# InputMicroproduct.net
KiCad netlist of a schematic drawn in Altium Designer
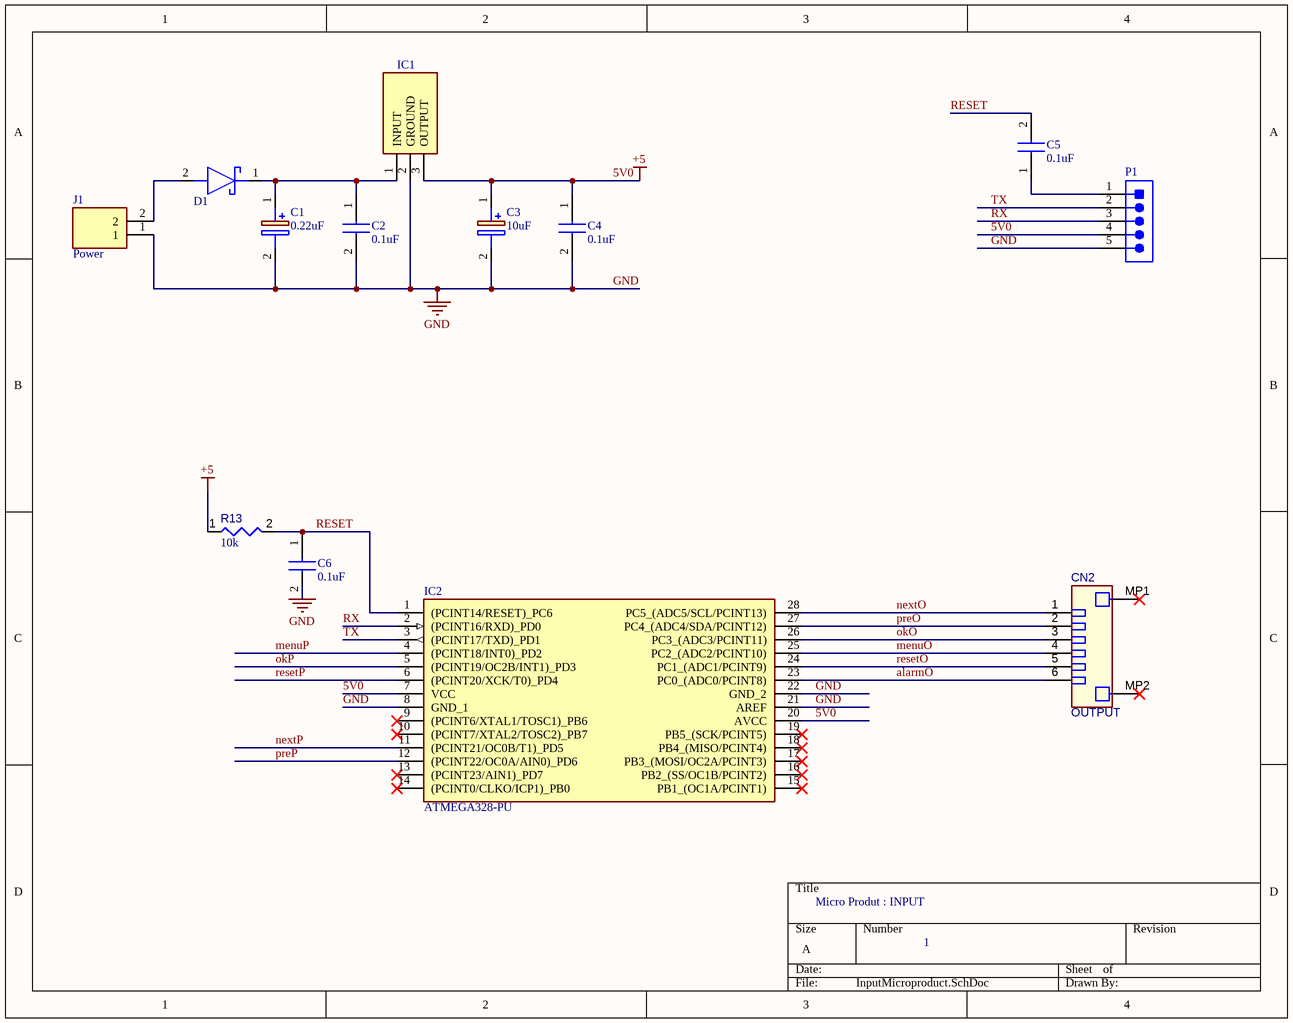
[diagram p0: InputMicroproduct.SchDoc]

(export (version "E")
  (design (tool "Eeschema 10.0.6"))
  (components
    (comp (ref "C1")
      (value "0.22uF")
      (footprint "SamacSys:CAPPRD200W52D500H1250")
      (description "Capacitor Polarised")
      (fields
        (field (name "MANUFACTURER_PART_NUMBER") "860010772002")
        (field (name "MOUSER PART NUMBER") "710-860010772002")
      )
      (libsource (lib "*") (part "860010772002"))
    )
    (comp (ref "C2")
      (value "0.1uF")
      (footprint "SamacSys:S104Z93Z5VL83L0R")
      (description "Capacitor")
      (fields
        (field (name "MANUFACTURER_PART_NUMBER") "S104Z93Z5VL83L0R")
        (field (name "MOUSER PART NUMBER") "594-S104Z93Z5VL83L0R")
      )
      (libsource (lib "*") (part "S104Z93Z5VL83L0R"))
    )
    (comp (ref "C3")
      (value "10uF")
      (footprint "SamacSys:CAPPRD200W55D500H1250")
      (description "Capacitor Polarised")
      (fields (field (name "MANUFACTURER_PART_NUMBER") "EEUFR1H100"))
      (libsource (lib "*") (part "EEUFR1H100"))
    )
    (comp (ref "C4")
      (value "0.1uF")
      (footprint "SamacSys:S104Z93Z5VL83L0R")
      (description "Capacitor")
      (fields
        (field (name "MANUFACTURER_PART_NUMBER") "S104Z93Z5VL83L0R")
        (field (name "MOUSER PART NUMBER") "594-S104Z93Z5VL83L0R")
      )
      (libsource (lib "*") (part "S104Z93Z5VL83L0R"))
    )
    (comp (ref "C5")
      (value "0.1uF")
      (footprint "SamacSys:S104Z93Z5VL83L0R")
      (description "Capacitor")
      (fields
        (field (name "MANUFACTURER_PART_NUMBER") "S104Z93Z5VL83L0R")
        (field (name "MOUSER PART NUMBER") "594-S104Z93Z5VL83L0R")
      )
      (libsource (lib "*") (part "S104Z93Z5VL83L0R"))
    )
    (comp (ref "C6")
      (value "0.1uF")
      (footprint "SamacSys:S104Z93Z5VL83L0R")
      (description "Capacitor")
      (fields
        (field (name "MANUFACTURER_PART_NUMBER") "S104Z93Z5VL83L0R")
        (field (name "MOUSER PART NUMBER") "594-S104Z93Z5VL83L0R")
      )
      (libsource (lib "*") (part "S104Z93Z5VL83L0R"))
    )
    (comp (ref "CN2")
      (value "OUTPUT")
      (footprint "JST-BM06B-SRSS-TB_V")
      (description "Header, Pitch 1 mm, 1 x 6 Position, Height 4.25 mm, -25 to 85 degC")
      (libsource (lib "University of Moratuwa") (part "CMP-00143-5"))
    )
    (comp (ref "D1")
      (value "Protection Diode")
      (footprint "SamacSys:DIOAD950W60L350D150")
      (description "Schottky Diode")
      (fields
        (field (name "MANUFACTURER_PART_NUMBER") "SD103A-TR")
        (field (name "MOUSER PART NUMBER") "625-SD103A")
      )
      (libsource (lib "*") (part "SD103A-TR"))
    )
    (comp (ref "IC1")
      (value "Power Regulator")
      (footprint "SamacSys:TO255P460X1020X2008-3P")
      (description "Integrated Circuit")
      (fields
        (field (name "MANUFACTURER_PART_NUMBER") "L7805CV")
        (field (name "MOUSER PART NUMBER") "511-L7805CV")
      )
      (libsource (lib "*") (part "L7805CV"))
    )
    (comp (ref "IC2")
      (value "ATMEGA328-PU")
      (footprint "SamacSys:DIP1016W53P254L3468H457Q28N")
      (description "Integrated Circuit")
      (fields (field (name "MOUSER PART NUMBER") "556-ATMEGA328-PU"))
      (libsource (lib "*") (part "ATMEGA328-PU"))
    )
    (comp (ref "J1")
      (value "1546215-2")
      (footprint "SamacSys:15462152")
      (description "Connector - Two pin (Power)")
      (fields (field (name "MOUSER PART NUMBER") "571-1546215-2") (field (name "TEXT") "Power"))
      (libsource (lib "*") (part "1546215-2"))
    )
    (comp (ref "P1")
      (value "77311-462K05LF")
      (footprint "FCI-77311-5_V")
      (fields (field (name "MANUFACTURER") "FCI Electronics"))
      (libsource (lib "University of Moratuwa") (part "CN-1P-M-R5"))
    )
    (comp (ref "R13")
      (value "10k")
      (footprint "RESA60-630X240")
      (description "Axial Resistor, 10 KOhm, +/- 1%, 0.25 W, -55 to 155 degC, 2-Pin THD, RoHS, Bulk")
      (fields (field (name "POWER") "250mW") (field (name "MANUFACTURER") "Yageo"))
      (libsource (lib "University of Moratuwa") (part "RES-2"))
    )
  )
  (nets
    (net (code "1") (name "+5") (class "Default")
      (node (ref "C3") (pin "1") (pinfunction "+_1") (pintype "passive"))
      (node (ref "C4") (pin "1") (pinfunction "1_1") (pintype "passive"))
      (node (ref "IC1") (pin "3") (pinfunction "OUTPUT_3") (pintype "passive"))
      (node (ref "IC2") (pin "20") (pinfunction "AVCC_20") (pintype "power_in"))
      (node (ref "IC2") (pin "7") (pinfunction "VCC_7") (pintype "power_in"))
      (node (ref "P1") (pin "4") (pinfunction "VCC_4") (pintype "passive"))
      (node (ref "R13") (pin "1") (pinfunction "1_1") (pintype "passive"))
    )
    (net (code "2") (name "/RESET") (class "Default")
      (node (ref "C5") (pin "2") (pinfunction "2_2") (pintype "passive"))
      (node (ref "C6") (pin "1") (pinfunction "1_1") (pintype "passive"))
      (node (ref "IC2") (pin "1") (pinfunction "(PCINT14/RESET)_PC6_1") (pintype "passive"))
      (node (ref "R13") (pin "2") (pinfunction "2_2") (pintype "passive"))
    )
    (net (code "3") (name "/RX") (class "Default")
      (node (ref "IC2") (pin "2") (pinfunction "(PCINT16/RXD)_PD0_2") (pintype "input"))
      (node (ref "P1") (pin "3") (pinfunction "TXO_3") (pintype "passive"))
    )
    (net (code "4") (name "/TX") (class "Default")
      (node (ref "IC2") (pin "3") (pinfunction "(PCINT17/TXD)_PD1_3") (pintype "output"))
      (node (ref "P1") (pin "2") (pinfunction "RXI_2") (pintype "passive"))
    )
    (net (code "5") (name "/alarmO") (class "Default")
      (node (ref "CN2") (pin "6") (pinfunction "6_6") (pintype "passive"))
      (node (ref "IC2") (pin "23") (pinfunction "PC0_(ADC0/PCINT8)_23") (pintype "passive"))
    )
    (net (code "6") (name "/menuO") (class "Default")
      (node (ref "CN2") (pin "4") (pinfunction "4_4") (pintype "passive"))
      (node (ref "IC2") (pin "25") (pinfunction "PC2_(ADC2/PCINT10)_25") (pintype "passive"))
    )
    (net (code "7") (name "/menuP") (class "Default")
      (node (ref "IC2") (pin "4") (pinfunction "(PCINT18/INT0)_PD2_4") (pintype "passive"))
    )
    (net (code "8") (name "/nextO") (class "Default")
      (node (ref "CN2") (pin "1") (pinfunction "1_1") (pintype "passive"))
      (node (ref "IC2") (pin "28") (pinfunction "PC5_(ADC5/SCL/PCINT13)_28") (pintype "passive"))
    )
    (net (code "9") (name "/nextP") (class "Default")
      (node (ref "IC2") (pin "11") (pinfunction "(PCINT21/OC0B/T1)_PD5_11") (pintype "passive"))
    )
    (net (code "10") (name "/okO") (class "Default")
      (node (ref "CN2") (pin "3") (pinfunction "3_3") (pintype "passive"))
      (node (ref "IC2") (pin "26") (pinfunction "PC3_(ADC3/PCINT11)_26") (pintype "passive"))
    )
    (net (code "11") (name "/okP") (class "Default")
      (node (ref "IC2") (pin "5") (pinfunction "(PCINT19/OC2B/INT1)_PD3_5") (pintype "passive"))
    )
    (net (code "12") (name "/preO") (class "Default")
      (node (ref "CN2") (pin "2") (pinfunction "2_2") (pintype "passive"))
      (node (ref "IC2") (pin "27") (pinfunction "PC4_(ADC4/SDA/PCINT12)_27") (pintype "passive"))
    )
    (net (code "13") (name "/preP") (class "Default")
      (node (ref "IC2") (pin "12") (pinfunction "(PCINT22/OC0A/AIN0)_PD6_12") (pintype "passive"))
    )
    (net (code "14") (name "/resetO") (class "Default")
      (node (ref "CN2") (pin "5") (pinfunction "5_5") (pintype "passive"))
      (node (ref "IC2") (pin "24") (pinfunction "PC1_(ADC1/PCINT9)_24") (pintype "passive"))
    )
    (net (code "15") (name "/resetP") (class "Default")
      (node (ref "IC2") (pin "6") (pinfunction "(PCINT20/XCK/T0)_PD4_6") (pintype "passive"))
    )
    (net (code "16") (name "GND") (class "Default")
      (node (ref "C1") (pin "2") (pinfunction "-_2") (pintype "passive"))
      (node (ref "C2") (pin "2") (pinfunction "2_2") (pintype "passive"))
      (node (ref "C3") (pin "2") (pinfunction "-_2") (pintype "passive"))
      (node (ref "C4") (pin "2") (pinfunction "2_2") (pintype "passive"))
      (node (ref "C6") (pin "2") (pinfunction "2_2") (pintype "passive"))
      (node (ref "IC1") (pin "2") (pinfunction "GROUND_2") (pintype "passive"))
      (node (ref "IC2") (pin "21") (pinfunction "AREF_21") (pintype "passive"))
      (node (ref "IC2") (pin "22") (pinfunction "GND_2_22") (pintype "power_in"))
      (node (ref "IC2") (pin "8") (pinfunction "GND_1_8") (pintype "power_in"))
      (node (ref "J1") (pin "1") (pinfunction "1_1") (pintype "passive"))
      (node (ref "P1") (pin "5") (pinfunction "CTS_5") (pintype "passive"))
    )
    (net (code "17") (name "Net-(C1-+)") (class "Default")
      (node (ref "C1") (pin "1") (pinfunction "+_1") (pintype "passive"))
      (node (ref "C2") (pin "1") (pinfunction "1_1") (pintype "passive"))
      (node (ref "D1") (pin "1") (pinfunction "K_1") (pintype "passive"))
      (node (ref "IC1") (pin "1") (pinfunction "INPUT_1") (pintype "passive"))
    )
    (net (code "18") (name "Net-(D1-A)") (class "Default")
      (node (ref "D1") (pin "2") (pinfunction "A_2") (pintype "passive"))
      (node (ref "J1") (pin "2") (pinfunction "2_2") (pintype "passive"))
    )
    (net (code "19") (name "Net-(P1-DTR)") (class "Default")
      (node (ref "C5") (pin "1") (pinfunction "1_1") (pintype "passive"))
      (node (ref "P1") (pin "1") (pinfunction "DTR_1") (pintype "passive"))
    )
    (net (code "20") (name "unconnected-(CN2-PadMP1)") (class "Default")
      (node (ref "CN2") (pin "MP1") (pinfunction "MP1_MP1") (pintype "passive+no_connect"))
    )
    (net (code "21") (name "unconnected-(CN2-PadMP2)") (class "Default")
      (node (ref "CN2") (pin "MP2") (pinfunction "MP2_MP2") (pintype "passive+no_connect"))
    )
    (net (code "22") (name "unconnected-(IC2-(PCINT0{slash}CLKO{slash}ICP1)_PB0-Pad14)") (class "Default")
      (node (ref "IC2") (pin "14") (pinfunction "(PCINT0/CLKO/ICP1)_PB0_14") (pintype "passive+no_connect"))
    )
    (net (code "23") (name "unconnected-(IC2-(PCINT6{slash}XTAL1{slash}TOSC1)_PB6-Pad9)") (class "Default")
      (node (ref "IC2") (pin "9") (pinfunction "(PCINT6/XTAL1/TOSC1)_PB6_9") (pintype "passive+no_connect"))
    )
    (net (code "24") (name "unconnected-(IC2-(PCINT7{slash}XTAL2{slash}TOSC2)_PB7-Pad10)") (class "Default")
      (node (ref "IC2") (pin "10") (pinfunction "(PCINT7/XTAL2/TOSC2)_PB7_10") (pintype "passive+no_connect"))
    )
    (net (code "25") (name "unconnected-(IC2-(PCINT23{slash}AIN1)_PD7-Pad13)") (class "Default")
      (node (ref "IC2") (pin "13") (pinfunction "(PCINT23/AIN1)_PD7_13") (pintype "passive+no_connect"))
    )
    (net (code "26") (name "unconnected-(IC2-PB1_(OC1A{slash}PCINT1)-Pad15)") (class "Default")
      (node (ref "IC2") (pin "15") (pinfunction "PB1_(OC1A/PCINT1)_15") (pintype "passive+no_connect"))
    )
    (net (code "27") (name "unconnected-(IC2-PB2_(SS{slash}OC1B{slash}PCINT2)-Pad16)") (class "Default")
      (node (ref "IC2") (pin "16") (pinfunction "PB2_(SS/OC1B/PCINT2)_16") (pintype "passive+no_connect"))
    )
    (net (code "28") (name "unconnected-(IC2-PB3_(MOSI{slash}OC2A{slash}PCINT3)-Pad17)") (class "Default")
      (node (ref "IC2") (pin "17") (pinfunction "PB3_(MOSI/OC2A/PCINT3)_17") (pintype "passive+no_connect"))
    )
    (net (code "29") (name "unconnected-(IC2-PB4_(MISO{slash}PCINT4)-Pad18)") (class "Default")
      (node (ref "IC2") (pin "18") (pinfunction "PB4_(MISO/PCINT4)_18") (pintype "passive+no_connect"))
    )
    (net (code "30") (name "unconnected-(IC2-PB5_(SCK{slash}PCINT5)-Pad19)") (class "Default")
      (node (ref "IC2") (pin "19") (pinfunction "PB5_(SCK/PCINT5)_19") (pintype "passive+no_connect"))
    )
  )
)
